# main_board.net
KiCad netlist of a schematic drawn in EAGLE
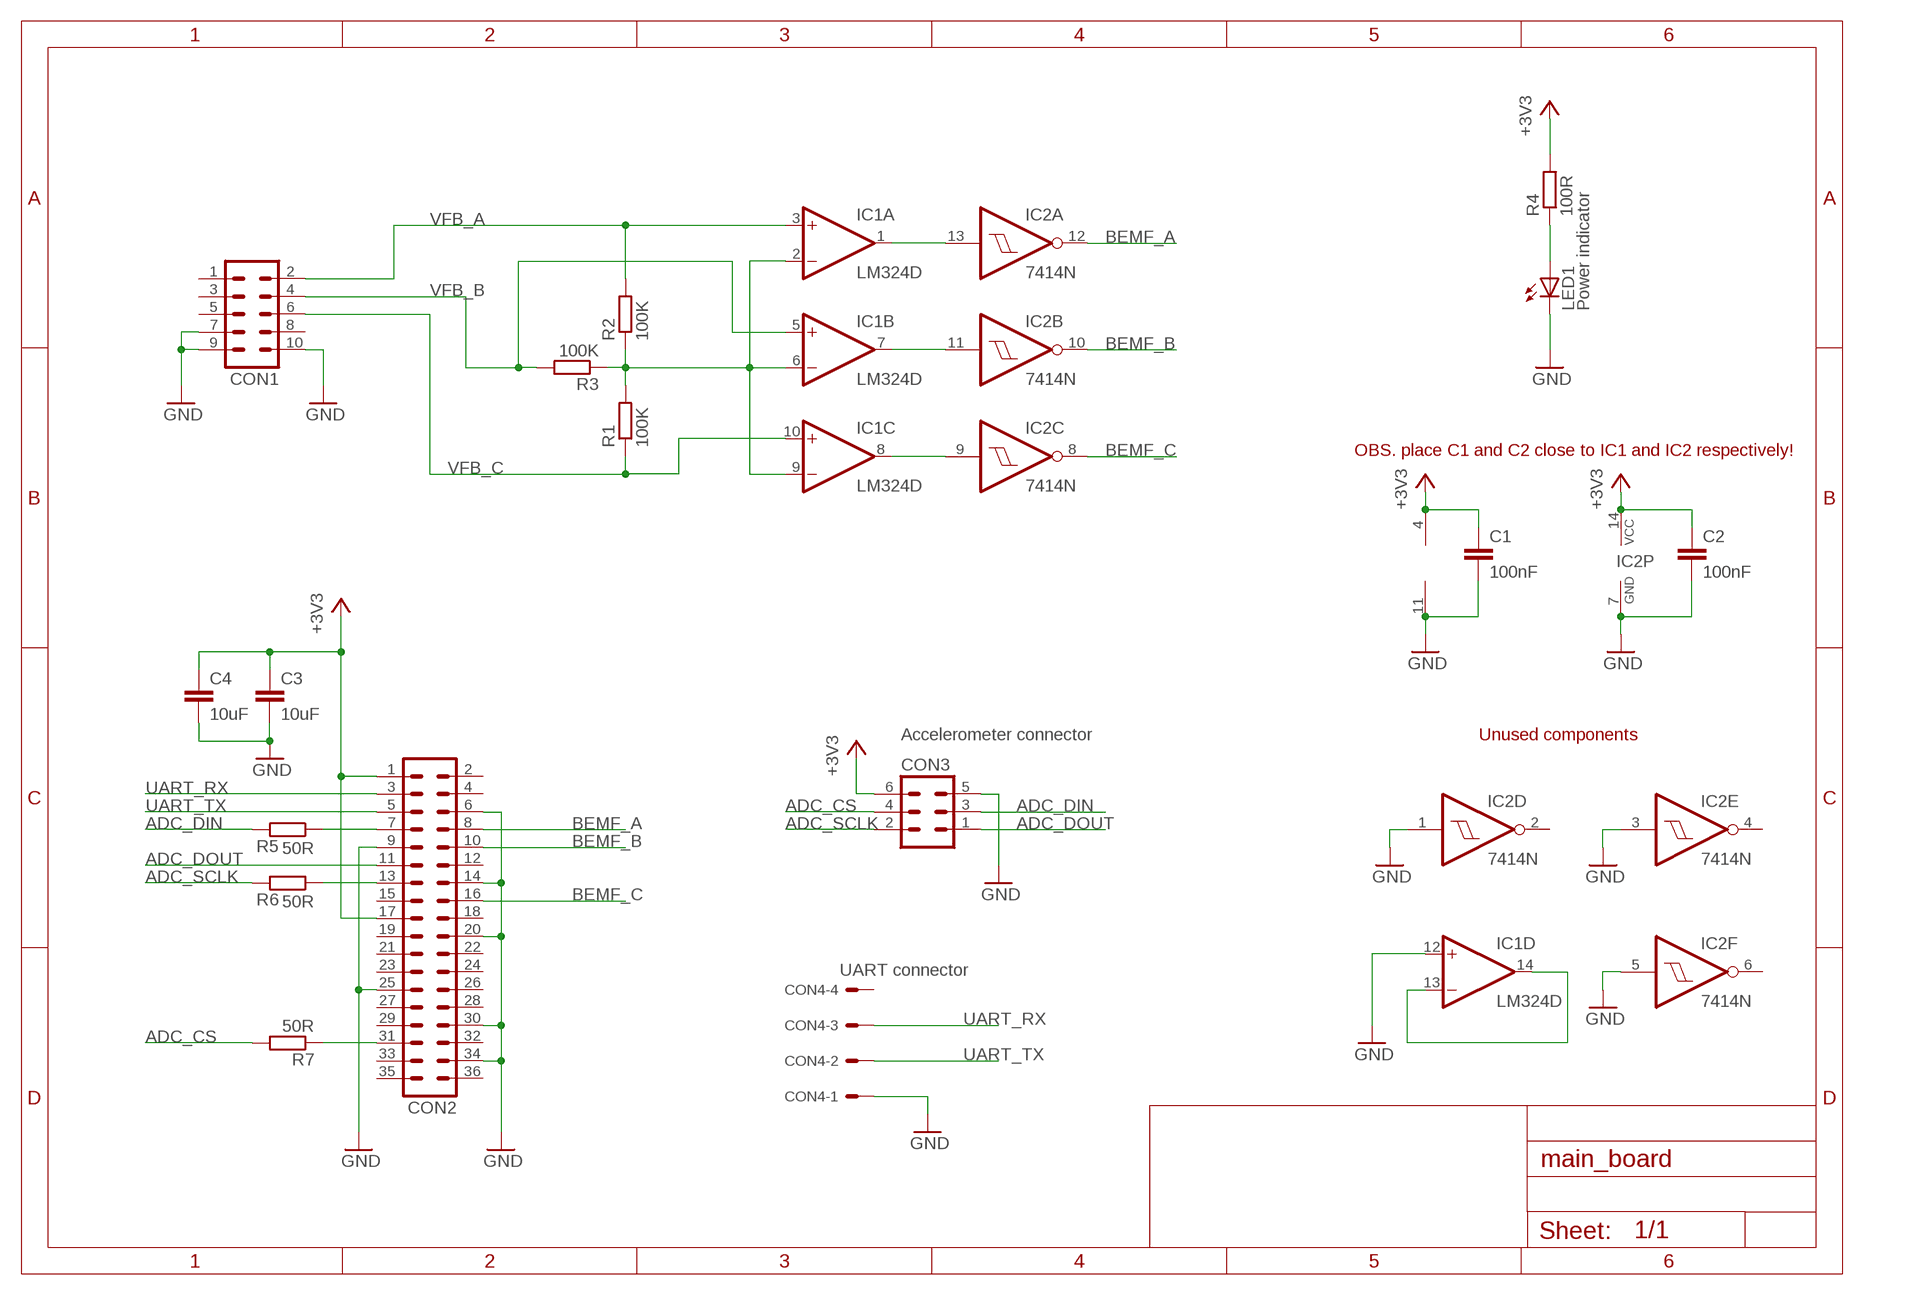
[diagram p0: schematic, sheet 1]

(export (version "E")
  (design (tool "Eeschema 10.0.6"))
  (components
    (comp (ref "C1")
      (value "100nF")
      (footprint "eagle-import:C0805K")
      (libsource (lib "eagle-import") (part "C-EUC0805K"))
    )
    (comp (ref "C2")
      (value "100nF")
      (footprint "eagle-import:C0805K")
      (libsource (lib "eagle-import") (part "C-EUC0805K"))
    )
    (comp (ref "C3")
      (value "10uF")
      (footprint "eagle-import:C1206K")
      (libsource (lib "eagle-import") (part "C-EUC1206K"))
    )
    (comp (ref "C4")
      (value "10uF")
      (footprint "eagle-import:C1206K")
      (libsource (lib "eagle-import") (part "C-EUC1206K"))
    )
    (comp (ref "CON1")
      (value "MA05-2")
      (footprint "eagle-import:MA05-2")
      (libsource (lib "eagle-import") (part "MA05-2"))
    )
    (comp (ref "CON2")
      (value "MA18-2")
      (footprint "eagle-import:MA18-2")
      (libsource (lib "eagle-import") (part "MA18-2"))
    )
    (comp (ref "CON3")
      (value "Accelerometer connector")
      (footprint "eagle-import:ML6")
      (libsource (lib "eagle-import") (part "ML6"))
    )
    (comp (ref "CON4")
      (value "UART connector")
      (footprint "eagle-import:6410-04")
      (libsource (lib "eagle-import") (part "22-?-0427-2041"))
    )
    (comp (ref "IC1")
      (value "LM324D")
      (footprint "eagle-import:SO14")
      (libsource (lib "eagle-import") (part "LM324D"))
    )
    (comp (ref "IC2")
      (value "7414N")
      (footprint "eagle-import:DIL14")
      (libsource (lib "eagle-import") (part "7414N"))
    )
    (comp (ref "LED1")
      (value "Power indicator")
      (footprint "eagle-import:CHIP-LED0805")
      (libsource (lib "eagle-import") (part "LEDCHIP-LED0805"))
    )
    (comp (ref "R1")
      (value "100K")
      (footprint "eagle-import:R0805")
      (libsource (lib "eagle-import") (part "R-EU_R0805"))
    )
    (comp (ref "R2")
      (value "100K")
      (footprint "eagle-import:R0805")
      (libsource (lib "eagle-import") (part "R-EU_R0805"))
    )
    (comp (ref "R3")
      (value "100K")
      (footprint "eagle-import:R0805")
      (libsource (lib "eagle-import") (part "R-EU_R0805"))
    )
    (comp (ref "R4")
      (value "100R")
      (footprint "eagle-import:R0805")
      (libsource (lib "eagle-import") (part "R-EU_R0805"))
    )
    (comp (ref "R5")
      (value "50R")
      (footprint "eagle-import:R0805")
      (libsource (lib "eagle-import") (part "R-EU_R0805"))
    )
    (comp (ref "R6")
      (value "50R")
      (footprint "eagle-import:R0805")
      (libsource (lib "eagle-import") (part "R-EU_R0805"))
    )
    (comp (ref "R7")
      (value "50R")
      (footprint "eagle-import:R0805")
      (libsource (lib "eagle-import") (part "R-EU_R0805"))
    )
  )
  (nets
    (net (code "1") (name "+3V3") (class "Default")
      (node (ref "C1") (pin "1") (pinfunction "1_1") (pintype "passive"))
      (node (ref "C2") (pin "1") (pinfunction "1_1") (pintype "passive"))
      (node (ref "C3") (pin "1") (pinfunction "1_1") (pintype "passive"))
      (node (ref "C4") (pin "1") (pinfunction "1_1") (pintype "passive"))
      (node (ref "CON2") (pin "1") (pinfunction "1_1") (pintype "passive"))
      (node (ref "CON2") (pin "17") (pinfunction "17_17") (pintype "passive"))
      (node (ref "CON3") (pin "6") (pinfunction "6_6") (pintype "passive"))
      (node (ref "IC1") (pin "4") (pinfunction "V+_4") (pintype "power_in"))
      (node (ref "IC2") (pin "14") (pinfunction "VCC_14") (pintype "power_in"))
      (node (ref "R4") (pin "2") (pinfunction "2_2") (pintype "passive"))
    )
    (net (code "2") (name "/ADC_CS") (class "Default")
      (node (ref "CON3") (pin "4") (pinfunction "4_4") (pintype "passive"))
      (node (ref "R7") (pin "2") (pinfunction "2_2") (pintype "passive"))
    )
    (net (code "3") (name "/ADC_DIN") (class "Default")
      (node (ref "CON3") (pin "3") (pinfunction "3_3") (pintype "passive"))
      (node (ref "R5") (pin "2") (pinfunction "2_2") (pintype "passive"))
    )
    (net (code "4") (name "/ADC_DOUT") (class "Default")
      (node (ref "CON2") (pin "11") (pinfunction "11_11") (pintype "passive"))
      (node (ref "CON3") (pin "1") (pinfunction "1_1") (pintype "passive"))
    )
    (net (code "5") (name "/ADC_SCLK") (class "Default")
      (node (ref "CON3") (pin "2") (pinfunction "2_2") (pintype "passive"))
      (node (ref "R6") (pin "2") (pinfunction "2_2") (pintype "passive"))
    )
    (net (code "6") (name "/BEMF_A") (class "Default")
      (node (ref "CON2") (pin "8") (pinfunction "8_8") (pintype "passive"))
      (node (ref "IC2") (pin "12") (pinfunction "O_12") (pintype "output"))
    )
    (net (code "7") (name "/BEMF_B") (class "Default")
      (node (ref "CON2") (pin "10") (pinfunction "10_10") (pintype "passive"))
      (node (ref "IC2") (pin "10") (pinfunction "O_10") (pintype "output"))
    )
    (net (code "8") (name "/BEMF_C") (class "Default")
      (node (ref "CON2") (pin "16") (pinfunction "16_16") (pintype "passive"))
      (node (ref "IC2") (pin "8") (pinfunction "O_8") (pintype "output"))
    )
    (net (code "9") (name "/UART_RX") (class "Default")
      (node (ref "CON2") (pin "3") (pinfunction "3_3") (pintype "passive"))
      (node (ref "CON4") (pin "3") (pinfunction "S_3") (pintype "passive"))
    )
    (net (code "10") (name "/UART_TX") (class "Default")
      (node (ref "CON2") (pin "5") (pinfunction "5_5") (pintype "passive"))
      (node (ref "CON4") (pin "2") (pinfunction "S_2") (pintype "passive"))
    )
    (net (code "11") (name "/VFB_A") (class "Default")
      (node (ref "CON1") (pin "2") (pinfunction "2_2") (pintype "passive"))
      (node (ref "IC1") (pin "3") (pinfunction "+IN_3") (pintype "input"))
      (node (ref "R2") (pin "2") (pinfunction "2_2") (pintype "passive"))
    )
    (net (code "12") (name "/VFB_B") (class "Default")
      (node (ref "CON1") (pin "4") (pinfunction "4_4") (pintype "passive"))
      (node (ref "IC1") (pin "5") (pinfunction "+IN_5") (pintype "input"))
      (node (ref "R3") (pin "2") (pinfunction "2_2") (pintype "passive"))
    )
    (net (code "13") (name "/VFB_C") (class "Default")
      (node (ref "CON1") (pin "6") (pinfunction "6_6") (pintype "passive"))
      (node (ref "IC1") (pin "10") (pinfunction "+IN_10") (pintype "input"))
      (node (ref "R1") (pin "1") (pinfunction "1_1") (pintype "passive"))
    )
    (net (code "14") (name "GND") (class "Default")
      (node (ref "C1") (pin "2") (pinfunction "2_2") (pintype "passive"))
      (node (ref "C2") (pin "2") (pinfunction "2_2") (pintype "passive"))
      (node (ref "C3") (pin "2") (pinfunction "2_2") (pintype "passive"))
      (node (ref "C4") (pin "2") (pinfunction "2_2") (pintype "passive"))
      (node (ref "CON1") (pin "10") (pinfunction "10_10") (pintype "passive"))
      (node (ref "CON1") (pin "7") (pinfunction "7_7") (pintype "passive"))
      (node (ref "CON1") (pin "9") (pinfunction "9_9") (pintype "passive"))
      (node (ref "CON2") (pin "14") (pinfunction "14_14") (pintype "passive"))
      (node (ref "CON2") (pin "20") (pinfunction "20_20") (pintype "passive"))
      (node (ref "CON2") (pin "25") (pinfunction "25_25") (pintype "passive"))
      (node (ref "CON2") (pin "30") (pinfunction "30_30") (pintype "passive"))
      (node (ref "CON2") (pin "34") (pinfunction "34_34") (pintype "passive"))
      (node (ref "CON2") (pin "6") (pinfunction "6_6") (pintype "passive"))
      (node (ref "CON2") (pin "9") (pinfunction "9_9") (pintype "passive"))
      (node (ref "CON3") (pin "5") (pinfunction "5_5") (pintype "passive"))
      (node (ref "CON4") (pin "1") (pinfunction "S_1") (pintype "passive"))
      (node (ref "IC1") (pin "11") (pinfunction "V-_11") (pintype "power_in"))
      (node (ref "IC1") (pin "12") (pinfunction "+IN_12") (pintype "input"))
      (node (ref "IC2") (pin "1") (pinfunction "I_1") (pintype "input"))
      (node (ref "IC2") (pin "3") (pinfunction "I_3") (pintype "input"))
      (node (ref "IC2") (pin "5") (pinfunction "I_5") (pintype "input"))
      (node (ref "IC2") (pin "7") (pinfunction "GND_7") (pintype "power_in"))
      (node (ref "LED1") (pin "C") (pinfunction "C_C") (pintype "passive"))
    )
    (net (code "15") (name "Net-(CON2-Pad7)") (class "Default")
      (node (ref "CON2") (pin "7") (pinfunction "7_7") (pintype "passive"))
      (node (ref "R5") (pin "1") (pinfunction "1_1") (pintype "passive"))
    )
    (net (code "16") (name "Net-(CON2-Pad13)") (class "Default")
      (node (ref "CON2") (pin "13") (pinfunction "13_13") (pintype "passive"))
      (node (ref "R6") (pin "1") (pinfunction "1_1") (pintype "passive"))
    )
    (net (code "17") (name "Net-(CON2-Pad31)") (class "Default")
      (node (ref "CON2") (pin "31") (pinfunction "31_31") (pintype "passive"))
      (node (ref "R7") (pin "1") (pinfunction "1_1") (pintype "passive"))
    )
    (net (code "18") (name "Net-(IC1A--IN)") (class "Default")
      (node (ref "IC1") (pin "2") (pinfunction "-IN_2") (pintype "input"))
      (node (ref "IC1") (pin "6") (pinfunction "-IN_6") (pintype "input"))
      (node (ref "IC1") (pin "9") (pinfunction "-IN_9") (pintype "input"))
      (node (ref "R1") (pin "2") (pinfunction "2_2") (pintype "passive"))
      (node (ref "R2") (pin "1") (pinfunction "1_1") (pintype "passive"))
      (node (ref "R3") (pin "1") (pinfunction "1_1") (pintype "passive"))
    )
    (net (code "19") (name "Net-(IC1A-OUT)") (class "Default")
      (node (ref "IC1") (pin "1") (pinfunction "OUT_1") (pintype "output"))
      (node (ref "IC2") (pin "13") (pinfunction "I_13") (pintype "input"))
    )
    (net (code "20") (name "Net-(IC1B-OUT)") (class "Default")
      (node (ref "IC1") (pin "7") (pinfunction "OUT_7") (pintype "output"))
      (node (ref "IC2") (pin "11") (pinfunction "I_11") (pintype "input"))
    )
    (net (code "21") (name "Net-(IC1C-OUT)") (class "Default")
      (node (ref "IC1") (pin "8") (pinfunction "OUT_8") (pintype "output"))
      (node (ref "IC2") (pin "9") (pinfunction "I_9") (pintype "input"))
    )
    (net (code "22") (name "Net-(IC1D--IN)") (class "Default")
      (node (ref "IC1") (pin "13") (pinfunction "-IN_13") (pintype "input"))
      (node (ref "IC1") (pin "14") (pinfunction "OUT_14") (pintype "output"))
    )
    (net (code "23") (name "Net-(LED1-PadA)") (class "Default")
      (node (ref "LED1") (pin "A") (pinfunction "A_A") (pintype "passive"))
      (node (ref "R4") (pin "1") (pinfunction "1_1") (pintype "passive"))
    )
    (net (code "24") (name "unconnected-(CON1-Pad1)") (class "Default")
      (node (ref "CON1") (pin "1") (pinfunction "1_1") (pintype "passive"))
    )
    (net (code "25") (name "unconnected-(CON1-Pad3)") (class "Default")
      (node (ref "CON1") (pin "3") (pinfunction "3_3") (pintype "passive"))
    )
    (net (code "26") (name "unconnected-(CON1-Pad5)") (class "Default")
      (node (ref "CON1") (pin "5") (pinfunction "5_5") (pintype "passive"))
    )
    (net (code "27") (name "unconnected-(CON1-Pad8)") (class "Default")
      (node (ref "CON1") (pin "8") (pinfunction "8_8") (pintype "passive"))
    )
    (net (code "28") (name "unconnected-(CON2-Pad2)") (class "Default")
      (node (ref "CON2") (pin "2") (pinfunction "2_2") (pintype "passive"))
    )
    (net (code "29") (name "unconnected-(CON2-Pad4)") (class "Default")
      (node (ref "CON2") (pin "4") (pinfunction "4_4") (pintype "passive"))
    )
    (net (code "30") (name "unconnected-(CON2-Pad12)") (class "Default")
      (node (ref "CON2") (pin "12") (pinfunction "12_12") (pintype "passive"))
    )
    (net (code "31") (name "unconnected-(CON2-Pad15)") (class "Default")
      (node (ref "CON2") (pin "15") (pinfunction "15_15") (pintype "passive"))
    )
    (net (code "32") (name "unconnected-(CON2-Pad18)") (class "Default")
      (node (ref "CON2") (pin "18") (pinfunction "18_18") (pintype "passive"))
    )
    (net (code "33") (name "unconnected-(CON2-Pad19)") (class "Default")
      (node (ref "CON2") (pin "19") (pinfunction "19_19") (pintype "passive"))
    )
    (net (code "34") (name "unconnected-(CON2-Pad21)") (class "Default")
      (node (ref "CON2") (pin "21") (pinfunction "21_21") (pintype "passive"))
    )
    (net (code "35") (name "unconnected-(CON2-Pad22)") (class "Default")
      (node (ref "CON2") (pin "22") (pinfunction "22_22") (pintype "passive"))
    )
    (net (code "36") (name "unconnected-(CON2-Pad23)") (class "Default")
      (node (ref "CON2") (pin "23") (pinfunction "23_23") (pintype "passive"))
    )
    (net (code "37") (name "unconnected-(CON2-Pad24)") (class "Default")
      (node (ref "CON2") (pin "24") (pinfunction "24_24") (pintype "passive"))
    )
    (net (code "38") (name "unconnected-(CON2-Pad26)") (class "Default")
      (node (ref "CON2") (pin "26") (pinfunction "26_26") (pintype "passive"))
    )
    (net (code "39") (name "unconnected-(CON2-Pad27)") (class "Default")
      (node (ref "CON2") (pin "27") (pinfunction "27_27") (pintype "passive"))
    )
    (net (code "40") (name "unconnected-(CON2-Pad28)") (class "Default")
      (node (ref "CON2") (pin "28") (pinfunction "28_28") (pintype "passive"))
    )
    (net (code "41") (name "unconnected-(CON2-Pad29)") (class "Default")
      (node (ref "CON2") (pin "29") (pinfunction "29_29") (pintype "passive"))
    )
    (net (code "42") (name "unconnected-(CON2-Pad32)") (class "Default")
      (node (ref "CON2") (pin "32") (pinfunction "32_32") (pintype "passive"))
    )
    (net (code "43") (name "unconnected-(CON2-Pad33)") (class "Default")
      (node (ref "CON2") (pin "33") (pinfunction "33_33") (pintype "passive"))
    )
    (net (code "44") (name "unconnected-(CON2-Pad35)") (class "Default")
      (node (ref "CON2") (pin "35") (pinfunction "35_35") (pintype "passive"))
    )
    (net (code "45") (name "unconnected-(CON2-Pad36)") (class "Default")
      (node (ref "CON2") (pin "36") (pinfunction "36_36") (pintype "passive"))
    )
    (net (code "46") (name "unconnected-(CON4D-S-Pad4)") (class "Default")
      (node (ref "CON4") (pin "4") (pinfunction "S_4") (pintype "passive"))
    )
    (net (code "47") (name "unconnected-(IC2D-O-Pad2)") (class "Default")
      (node (ref "IC2") (pin "2") (pinfunction "O_2") (pintype "output"))
    )
    (net (code "48") (name "unconnected-(IC2E-O-Pad4)") (class "Default")
      (node (ref "IC2") (pin "4") (pinfunction "O_4") (pintype "output"))
    )
    (net (code "49") (name "unconnected-(IC2F-O-Pad6)") (class "Default")
      (node (ref "IC2") (pin "6") (pinfunction "O_6") (pintype "output"))
    )
  )
)
